# Schematic.net
KiCad netlist of a schematic drawn in EAGLE
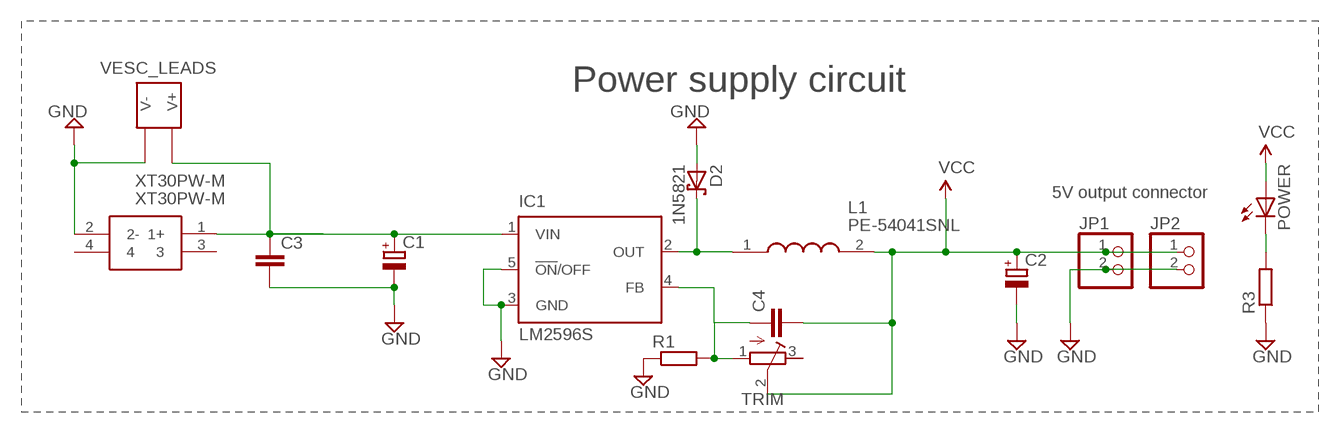
[diagram p0: schematic, sheet 1]

(export (version "E")
  (design (tool "Eeschema 10.0.6"))
  (components
    (comp (ref "C1")
      (value "CPOL-EUE5-13")
      (footprint "eagle-import:E5-13")
      (libsource (lib "eagle-import") (part "CPOL-EUE5-13"))
    )
    (comp (ref "C2")
      (value "CPOL-EUE2.5-7")
      (footprint "eagle-import:E2,5-7")
      (libsource (lib "eagle-import") (part "CPOL-EUE2.5-7"))
    )
    (comp (ref "C3")
      (value "C-EUC1206")
      (footprint "eagle-import:C1206")
      (libsource (lib "eagle-import") (part "C-EUC1206"))
    )
    (comp (ref "C4")
      (value "C2,5-3")
      (footprint "eagle-import:C2.5-3")
      (libsource (lib "eagle-import") (part "C2,5-3"))
    )
    (comp (ref "D2")
      (value "1N5821")
      (footprint "eagle-import:DO41-7.6")
      (libsource (lib "eagle-import") (part "1N5819-T"))
    )
    (comp (ref "IC1")
      (value "LM2596S")
      (footprint "eagle-import:TO263-5")
      (fields (field (name "MF") "NATIONAL SEMICONDUCTOR") (field (name "MPN") "LM2596S-ADJ/NOPB"))
      (libsource (lib "eagle-import") (part "LM2596S"))
    )
    (comp (ref "JP1")
      (value "PINHD-1X2")
      (footprint "eagle-import:1X02")
      (libsource (lib "eagle-import") (part "PINHD-1X2"))
    )
    (comp (ref "JP2")
      (value "PINHD-1X2")
      (footprint "eagle-import:1X02")
      (libsource (lib "eagle-import") (part "PINHD-1X2"))
    )
    (comp (ref "L1")
      (value "PE-54041SNL")
      (footprint "eagle-import:P0846SNLT")
      (fields (field (name "MOUSER_PART_NUMBER") "673-PE-54041SNL"))
      (libsource (lib "eagle-import") (part "PE-54041SNL"))
    )
    (comp (ref "POWER")
      (value "LEDSML0805")
      (footprint "eagle-import:SML0805")
      (libsource (lib "eagle-import") (part "LEDSML0805"))
    )
    (comp (ref "R1")
      (value "R-EU_0204/7")
      (footprint "eagle-import:0204_7")
      (libsource (lib "eagle-import") (part "R-EU_0204/7"))
    )
    (comp (ref "R3")
      (value "R-EU_R1206")
      (footprint "eagle-import:R1206")
      (libsource (lib "eagle-import") (part "resistor_348_R-EU_R1206"))
    )
    (comp (ref "TRIM")
      (value "R-TRIMM3296W")
      (footprint "eagle-import:RTRIM3296W")
      (libsource (lib "eagle-import") (part "R-TRIMM3296W"))
    )
    (comp (ref "U$1")
      (value "VESC_LEADS")
      (footprint "eagle-import:VESC_LEADS")
      (libsource (lib "eagle-import") (part "VESC_LEADS"))
    )
    (comp (ref "XT30PW-M")
      (value "XT30PW-M")
      (footprint "eagle-import:XT30PWM")
      (libsource (lib "eagle-import") (part "XT30PW-M"))
    )
  )
  (nets
    (net (code "1") (name "GND") (class "Default")
      (node (ref "C1") (pin "-") (pinfunction "-_-") (pintype "passive"))
      (node (ref "C2") (pin "-") (pinfunction "-_-") (pintype "passive"))
      (node (ref "C3") (pin "2") (pinfunction "2_2") (pintype "passive"))
      (node (ref "D2") (pin "A") (pinfunction "A_A") (pintype "passive"))
      (node (ref "IC1") (pin "3") (pinfunction "GND_3") (pintype "power_in"))
      (node (ref "IC1") (pin "5") (pinfunction "~{ON}/OFF_5") (pintype "input"))
      (node (ref "JP1") (pin "2") (pinfunction "2_2") (pintype "passive"))
      (node (ref "JP2") (pin "2") (pinfunction "2_2") (pintype "passive"))
      (node (ref "R1") (pin "1") (pinfunction "1_1") (pintype "passive"))
      (node (ref "R3") (pin "1") (pinfunction "1_1") (pintype "passive"))
      (node (ref "U$1") (pin "P$2") (pinfunction "V-_P$2") (pintype "bidirectional"))
      (node (ref "XT30PW-M") (pin "2") (pinfunction "2-_2") (pintype "bidirectional"))
    )
    (net (code "2") (name "Net-(IC1-FB)") (class "Default")
      (node (ref "C4") (pin "1") (pinfunction "1_1") (pintype "passive"))
      (node (ref "IC1") (pin "4") (pinfunction "FB_4") (pintype "input"))
      (node (ref "R1") (pin "2") (pinfunction "2_2") (pintype "passive"))
      (node (ref "TRIM") (pin "1") (pinfunction "A_1") (pintype "passive"))
    )
    (net (code "3") (name "Net-(IC1-OUT)") (class "Default")
      (node (ref "D2") (pin "C") (pinfunction "C_C") (pintype "passive"))
      (node (ref "IC1") (pin "2") (pinfunction "OUT_2") (pintype "output"))
      (node (ref "L1") (pin "1") (pinfunction "1_1") (pintype "bidirectional"))
    )
    (net (code "4") (name "Net-(IC1-VIN)") (class "Default")
      (node (ref "C1") (pin "+") (pinfunction "+_+") (pintype "passive"))
      (node (ref "C3") (pin "1") (pinfunction "1_1") (pintype "passive"))
      (node (ref "IC1") (pin "1") (pinfunction "VIN_1") (pintype "input"))
      (node (ref "U$1") (pin "P$1") (pinfunction "V+_P$1") (pintype "bidirectional"))
      (node (ref "XT30PW-M") (pin "1") (pinfunction "1+_1") (pintype "bidirectional"))
    )
    (net (code "5") (name "Net-(POWER-PadC)") (class "Default")
      (node (ref "POWER") (pin "C") (pinfunction "C_C") (pintype "passive"))
      (node (ref "R3") (pin "2") (pinfunction "2_2") (pintype "passive"))
    )
    (net (code "6") (name "VCC") (class "Default")
      (node (ref "C2") (pin "+") (pinfunction "+_+") (pintype "passive"))
      (node (ref "C4") (pin "2") (pinfunction "2_2") (pintype "passive"))
      (node (ref "JP1") (pin "1") (pinfunction "1_1") (pintype "passive"))
      (node (ref "JP2") (pin "1") (pinfunction "1_1") (pintype "passive"))
      (node (ref "L1") (pin "2") (pinfunction "2_2") (pintype "bidirectional"))
      (node (ref "POWER") (pin "A") (pinfunction "A_A") (pintype "passive"))
      (node (ref "TRIM") (pin "2") (pinfunction "S_2") (pintype "passive"))
    )
    (net (code "7") (name "unconnected-(TRIM-E-Pad3)") (class "Default")
      (node (ref "TRIM") (pin "3") (pinfunction "E_3") (pintype "passive"))
    )
    (net (code "8") (name "unconnected-(XT30PW-M-Pad3)") (class "Default")
      (node (ref "XT30PW-M") (pin "3") (pinfunction "3_3") (pintype "bidirectional"))
    )
    (net (code "9") (name "unconnected-(XT30PW-M-Pad4)") (class "Default")
      (node (ref "XT30PW-M") (pin "4") (pinfunction "4_4") (pintype "bidirectional"))
    )
  )
)
